# MCU.net
KiCad netlist of a schematic drawn in Altium Designer
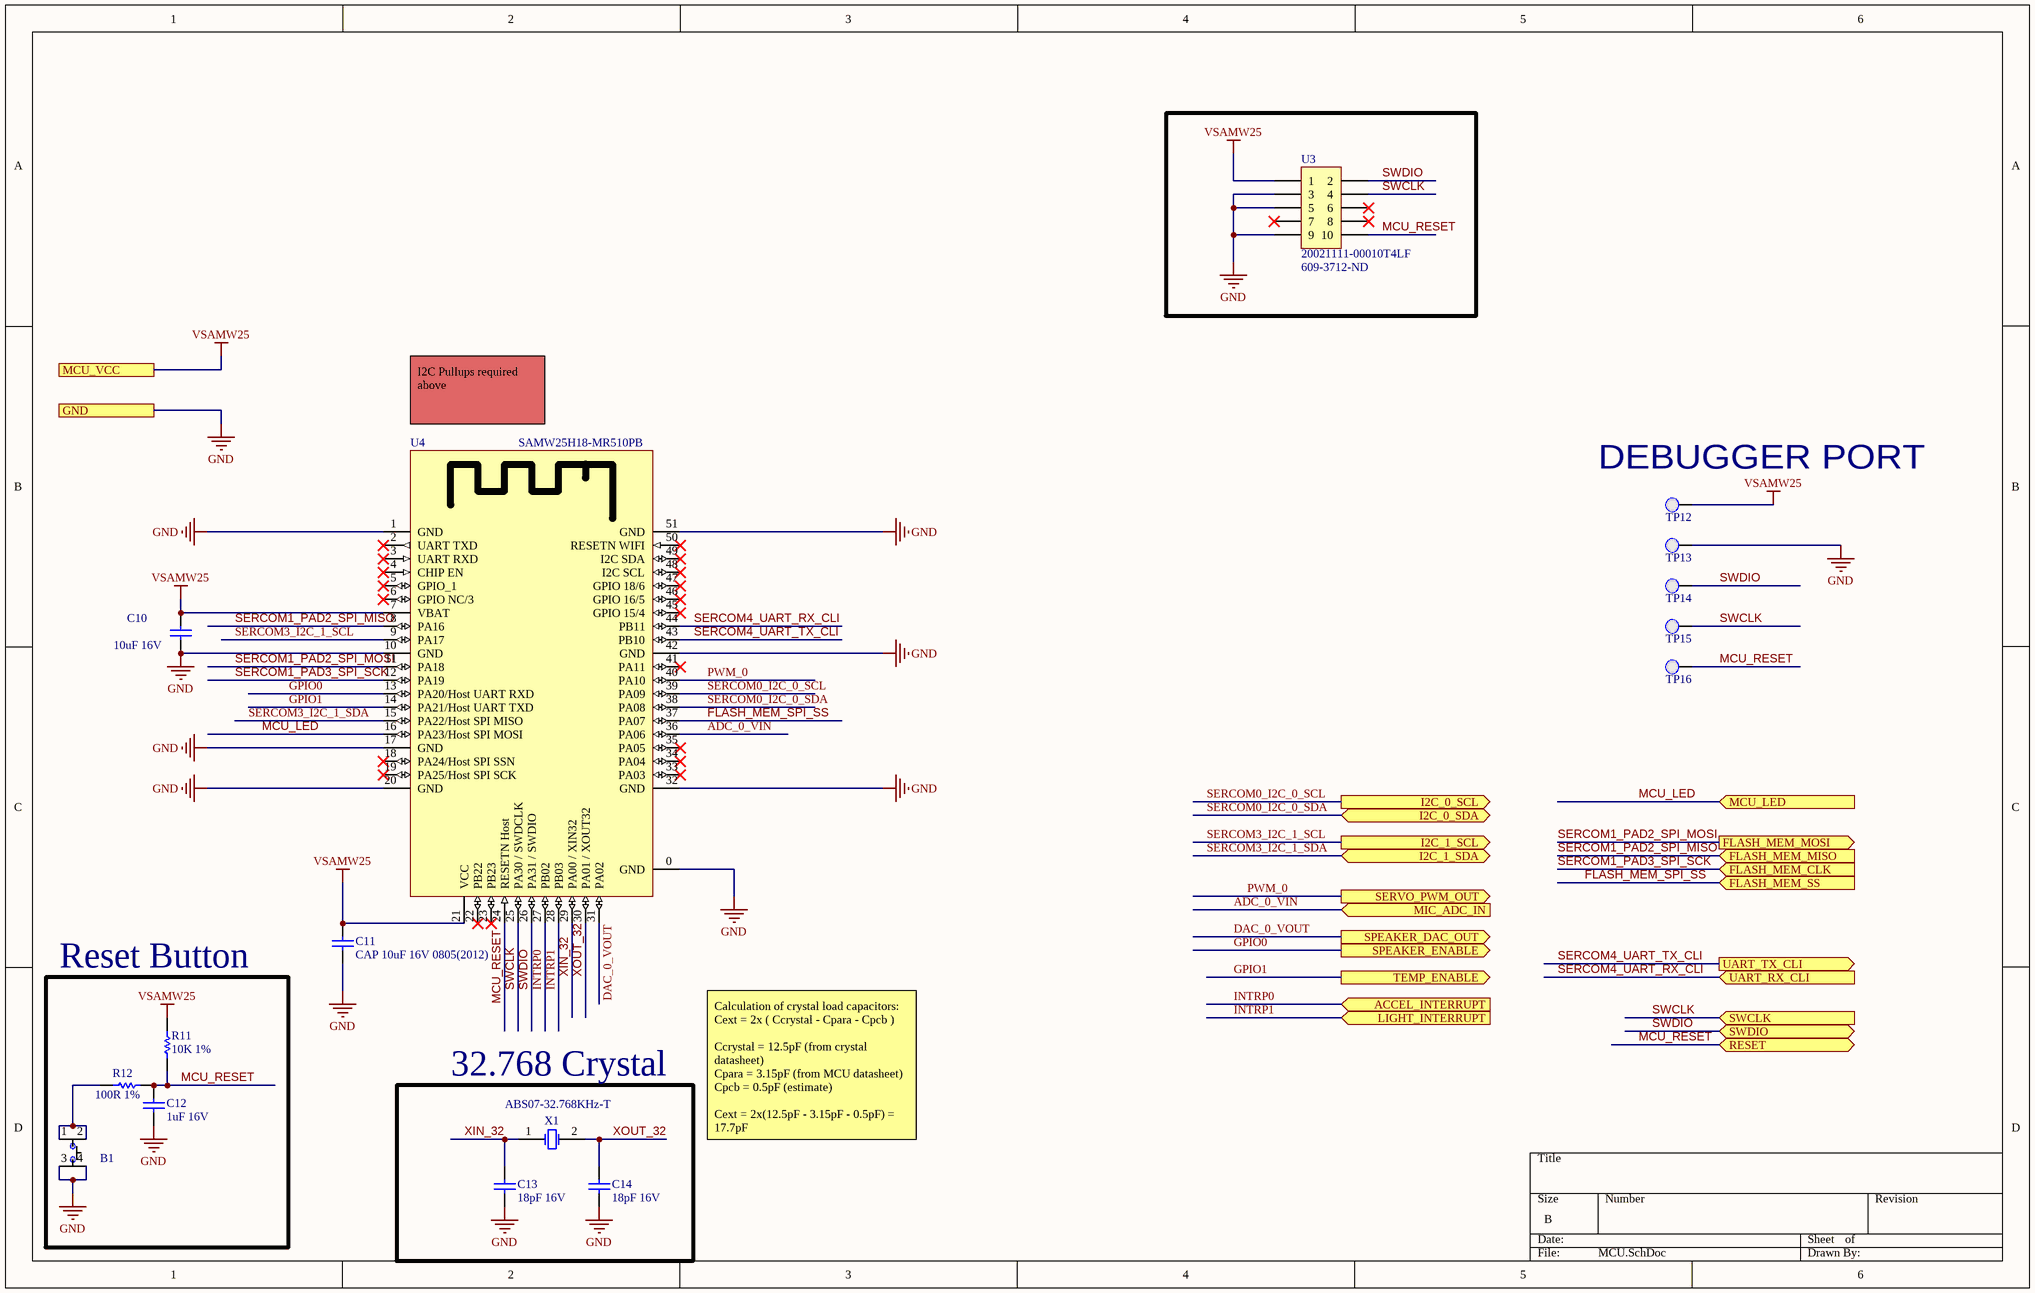
[diagram p0: MCU.SchDoc]

(export (version "E")
  (design (tool "Eeschema 10.0.6"))
  (components
    (comp (ref "B1")
      (value "PTS810 SJK 250 SMTR LFS")
      (footprint "PTS810 SJK 250 SMTR LFS")
      (description "SWITCH TACTILE SPST-NO 0.05A 16V Tactile Switch SPST-NO Top Actuated Surface Mount")
      (fields
        (field (name "MANUFACTURER") "ITT /  C&K Components")
        (field (name "MANUFACTURER PART NUMBER") "PTS810SJK250SMTRLFS")
      )
      (libsource (lib "Schematics") (part "PTS810 SJK 250 SMTR LFS"))
    )
    (comp (ref "C10")
      (value "10uF 16V")
      (footprint "CAPC0805(2012)145_N")
      (description "CAP 10uF 16V ±10% 0805 (2012 Metric) Thickness 1.45mm SMD")
      (fields (field (name "TOLERANCE") "Â±10%"))
      (libsource (lib "Altium Content Vault") (part "CAP"))
    )
    (comp (ref "C11")
      (value "CAP 10uF 16V 0805(2012)")
      (footprint "CAPC0805(2012)145_N")
      (description "CAP 10uF 16V ±10% 0805 (2012 Metric) Thickness 1.45mm SMD")
      (fields (field (name "TOLERANCE") "Â±10%"))
      (libsource (lib "Altium Content Vault") (part "CAP"))
    )
    (comp (ref "C12")
      (value "1uF 16V")
      (footprint "CAPC0603(1608)100_N")
      (description "CAP 1uF 16V ±5% 0603 (1608 Metric) Thickness 1mm SMD")
      (fields (field (name "TOLERANCE") "Â±5%"))
      (libsource (lib "Altium Content Vault") (part "CAP"))
    )
    (comp (ref "C13")
      (value "18pF 16V")
      (footprint "CAPC0603(1608)100_N")
      (description "CAP 18pF 16V ±5% 0603 (1608 Metric) Thickness 1mm SMD")
      (fields (field (name "TOLERANCE") "Â±5%"))
      (libsource (lib "Altium Content Vault") (part "CAP"))
    )
    (comp (ref "C14")
      (value "18pF 16V")
      (footprint "CAPC0603(1608)100_N")
      (description "CAP 18pF 16V ±5% 0603 (1608 Metric) Thickness 1mm SMD")
      (fields (field (name "TOLERANCE") "Â±5%"))
      (libsource (lib "Altium Content Vault") (part "CAP"))
    )
    (comp (ref "R11")
      (value "10K 1%")
      (footprint "RESC0603(1608)_N")
      (description "10K 0.1W 1% 0603 (1608 Metric)  SMD")
      (fields (field (name "POWER") "0.1 W") (field (name "TOLERANCE") "1 %"))
      (libsource (lib "Altium Content Vault") (part "RES"))
    )
    (comp (ref "R12")
      (value "100R 1%")
      (footprint "RESC0603(1608)_N")
      (description "100R 0.1W 1% 0603 (1608 Metric)  SMD")
      (fields (field (name "TOLERANCE") "1 %") (field (name "POWER") "0.1 W"))
      (libsource (lib "Altium Content Vault") (part "RES"))
    )
    (comp (ref "TP12")
      (value "0.1\" Pad")
      (footprint "PCBComponent")
      (libsource (lib "Components - 12.02.20 - 18.05") (part "0.1{dblquote} Pad-A.4"))
    )
    (comp (ref "TP13")
      (value "0.1\" Pad")
      (footprint "PCBComponent")
      (libsource (lib "Components - 12.02.20 - 18.05") (part "0.1{dblquote} Pad-A.4"))
    )
    (comp (ref "TP14")
      (value "0.1\" Pad")
      (footprint "PCBComponent")
      (libsource (lib "Components - 12.02.20 - 18.05") (part "0.1{dblquote} Pad-A.4"))
    )
    (comp (ref "TP15")
      (value "0.1\" Pad")
      (footprint "PCBComponent")
      (libsource (lib "Components - 12.02.20 - 18.05") (part "0.1{dblquote} Pad-A.4"))
    )
    (comp (ref "TP16")
      (value "0.1\" Pad")
      (footprint "PCBComponent")
      (libsource (lib "Components - 12.02.20 - 18.05") (part "0.1{dblquote} Pad-A.4"))
    )
    (comp (ref "U3")
      (value "20021111-00010T4LF")
      (footprint "20021111-00010T4LF")
      (description "CONN HEADER 10POS UNSHD VERT T/H")
      (fields
        (field (name "MANUFACTURER") "Amphenol / FCI")
        (field (name "SUPPLIER PART NUMBER 1") "609-3712-ND")
      )
      (libsource (lib "Schematics") (part "20021111-00010T4LF"))
    )
    (comp (ref "U4")
      (value "SAMW25H18-MR510PB")
      (footprint "SAMW25H18-MR510PB")
      (description "RF TXRX MODULE WIFI TRACE ANT")
      (fields
        (field (name "MANUFACTURER") "Atmel")
        (field (name "MANUFACTURER PART NUMBER") "ATSAMW25H18-MR510PB")
      )
      (libsource (lib "Schematics") (part "SAMW25H18-MR510PB"))
    )
    (comp (ref "X1")
      (value "ABS07-32.768KHz-T")
      (footprint "ABRA-ABS07-2_V")
      (description "Crystal, 32.768 kHz, 12.5 pF, -40 to 85 degC, SMD Low Profile 3.2 x 1.5 x 0.9 mm, Tape and Reel")
      (fields (field (name "MANUFACTURER") "Abracon"))
      (libsource (lib "Altium Content Vault") (part "ABRA-ABS07-2"))
    )
  )
  (nets
    (net (code "1") (name "/ADC_0_VIN") (class "Default")
      (node (ref "U4") (pin "36") (pinfunction "PA06_36") (pintype "bidirectional"))
    )
    (net (code "2") (name "/DAC_0_VOUT") (class "Default")
      (node (ref "U4") (pin "31") (pinfunction "PA02_31") (pintype "bidirectional"))
    )
    (net (code "3") (name "/FLASH_MEM_SPI_SS") (class "Default")
      (node (ref "U4") (pin "37") (pinfunction "PA07_37") (pintype "bidirectional"))
    )
    (net (code "4") (name "/GPIO0") (class "Default")
      (node (ref "U4") (pin "13") (pinfunction "PA20/Host_UART_RXD_13") (pintype "bidirectional"))
    )
    (net (code "5") (name "/GPIO1") (class "Default")
      (node (ref "U4") (pin "14") (pinfunction "PA21/Host_UART_TXD_14") (pintype "bidirectional"))
    )
    (net (code "6") (name "/INTRP0") (class "Default")
      (node (ref "U4") (pin "27") (pinfunction "PB02_27") (pintype "bidirectional"))
    )
    (net (code "7") (name "/INTRP1") (class "Default")
      (node (ref "U4") (pin "28") (pinfunction "PB03_28") (pintype "bidirectional"))
    )
    (net (code "8") (name "/MCU_LED") (class "Default")
      (node (ref "U4") (pin "16") (pinfunction "PA23/Host_SPI_MOSI_16") (pintype "bidirectional"))
    )
    (net (code "9") (name "/MCU_RESET") (class "Default")
      (node (ref "C12") (pin "2") (pinfunction "2_2") (pintype "passive"))
      (node (ref "R11") (pin "1") (pinfunction "1_1") (pintype "passive"))
      (node (ref "R12") (pin "2") (pinfunction "2_2") (pintype "passive"))
      (node (ref "TP16") (pin "1") (pinfunction "PAD_1") (pintype "passive"))
      (node (ref "U3") (pin "10") (pinfunction "10_10") (pintype "passive"))
      (node (ref "U4") (pin "24") (pinfunction "RESETN_Host_24") (pintype "input"))
    )
    (net (code "10") (name "/PWM_0") (class "Default")
      (node (ref "U4") (pin "40") (pinfunction "PA10_40") (pintype "bidirectional"))
    )
    (net (code "11") (name "/SERCOM0_I2C_0_SCL") (class "Default")
      (node (ref "U4") (pin "39") (pinfunction "PA09_39") (pintype "bidirectional"))
    )
    (net (code "12") (name "/SERCOM0_I2C_0_SDA") (class "Default")
      (node (ref "U4") (pin "38") (pinfunction "PA08_38") (pintype "bidirectional"))
    )
    (net (code "13") (name "/SERCOM1_PAD2_SPI_MISO") (class "Default")
      (node (ref "U4") (pin "8") (pinfunction "PA16_8") (pintype "bidirectional"))
    )
    (net (code "14") (name "/SERCOM1_PAD2_SPI_MOSI") (class "Default")
      (node (ref "U4") (pin "11") (pinfunction "PA18_11") (pintype "bidirectional"))
    )
    (net (code "15") (name "/SERCOM1_PAD3_SPI_SCK") (class "Default")
      (node (ref "U4") (pin "12") (pinfunction "PA19_12") (pintype "bidirectional"))
    )
    (net (code "16") (name "/SERCOM3_I2C_1_SCL") (class "Default")
      (node (ref "U4") (pin "9") (pinfunction "PA17_9") (pintype "bidirectional"))
    )
    (net (code "17") (name "/SERCOM3_I2C_1_SDA") (class "Default")
      (node (ref "U4") (pin "15") (pinfunction "PA22/Host_SPI_MISO_15") (pintype "bidirectional"))
    )
    (net (code "18") (name "/SERCOM4_UART_RX_CLI") (class "Default")
      (node (ref "U4") (pin "44") (pinfunction "PB11_44") (pintype "bidirectional"))
    )
    (net (code "19") (name "/SERCOM4_UART_TX_CLI") (class "Default")
      (node (ref "U4") (pin "43") (pinfunction "PB10_43") (pintype "bidirectional"))
    )
    (net (code "20") (name "/SWCLK") (class "Default")
      (node (ref "TP15") (pin "1") (pinfunction "PAD_1") (pintype "passive"))
      (node (ref "U3") (pin "4") (pinfunction "4_4") (pintype "passive"))
      (node (ref "U4") (pin "25") (pinfunction "PA30_/_SWDCLK_25") (pintype "bidirectional"))
    )
    (net (code "21") (name "/SWDIO") (class "Default")
      (node (ref "TP14") (pin "1") (pinfunction "PAD_1") (pintype "passive"))
      (node (ref "U3") (pin "2") (pinfunction "2_2") (pintype "passive"))
      (node (ref "U4") (pin "26") (pinfunction "PA31_/_SWDIO_26") (pintype "bidirectional"))
    )
    (net (code "22") (name "/XIN_32") (class "Default")
      (node (ref "C13") (pin "2") (pinfunction "2_2") (pintype "passive"))
      (node (ref "U4") (pin "29") (pinfunction "PA00_/_XIN32_29") (pintype "bidirectional"))
      (node (ref "X1") (pin "1") (pinfunction "X1_1") (pintype "passive"))
    )
    (net (code "23") (name "/XOUT_32") (class "Default")
      (node (ref "C14") (pin "2") (pinfunction "2_2") (pintype "passive"))
      (node (ref "U4") (pin "30") (pinfunction "PA01_/_XOUT32_30") (pintype "bidirectional"))
      (node (ref "X1") (pin "2") (pinfunction "X2_2") (pintype "passive"))
    )
    (net (code "24") (name "GND") (class "Default")
      (node (ref "B1") (pin "3") (pinfunction "3_3") (pintype "power_in"))
      (node (ref "B1") (pin "4") (pinfunction "4_4") (pintype "power_in"))
      (node (ref "C10") (pin "1") (pinfunction "1_1") (pintype "passive"))
      (node (ref "C11") (pin "1") (pinfunction "1_1") (pintype "passive"))
      (node (ref "C12") (pin "1") (pinfunction "1_1") (pintype "passive"))
      (node (ref "C13") (pin "1") (pinfunction "1_1") (pintype "passive"))
      (node (ref "C14") (pin "1") (pinfunction "1_1") (pintype "passive"))
      (node (ref "TP13") (pin "1") (pinfunction "PAD_1") (pintype "passive"))
      (node (ref "U3") (pin "3") (pinfunction "3_3") (pintype "passive"))
      (node (ref "U3") (pin "5") (pinfunction "5_5") (pintype "passive"))
      (node (ref "U3") (pin "9") (pinfunction "9_9") (pintype "passive"))
      (node (ref "U4") (pin "0") (pinfunction "GND_0") (pintype "power_in"))
      (node (ref "U4") (pin "1") (pinfunction "GND_1") (pintype "power_in"))
      (node (ref "U4") (pin "10") (pinfunction "GND_10") (pintype "power_in"))
      (node (ref "U4") (pin "17") (pinfunction "GND_17") (pintype "power_in"))
      (node (ref "U4") (pin "20") (pinfunction "GND_20") (pintype "power_in"))
      (node (ref "U4") (pin "32") (pinfunction "GND_32") (pintype "power_in"))
      (node (ref "U4") (pin "42") (pinfunction "GND_42") (pintype "power_in"))
      (node (ref "U4") (pin "51") (pinfunction "GND_51") (pintype "power_in"))
    )
    (net (code "25") (name "Net-(B1-Pad1)") (class "Default")
      (node (ref "B1") (pin "1") (pinfunction "1_1") (pintype "power_in"))
      (node (ref "B1") (pin "2") (pinfunction "2_2") (pintype "power_in"))
      (node (ref "R12") (pin "1") (pinfunction "1_1") (pintype "passive"))
    )
    (net (code "26") (name "VSAMW25") (class "Default")
      (node (ref "C10") (pin "2") (pinfunction "2_2") (pintype "passive"))
      (node (ref "C11") (pin "2") (pinfunction "2_2") (pintype "passive"))
      (node (ref "R11") (pin "2") (pinfunction "2_2") (pintype "passive"))
      (node (ref "TP12") (pin "1") (pinfunction "PAD_1") (pintype "passive"))
      (node (ref "U3") (pin "1") (pinfunction "1_1") (pintype "passive"))
      (node (ref "U4") (pin "21") (pinfunction "VCC_21") (pintype "power_in"))
      (node (ref "U4") (pin "7") (pinfunction "VBAT_7") (pintype "power_in"))
    )
    (net (code "27") (name "unconnected-(U3-Pad6)") (class "Default")
      (node (ref "U3") (pin "6") (pinfunction "6_6") (pintype "passive+no_connect"))
    )
    (net (code "28") (name "unconnected-(U3-Pad7)") (class "Default")
      (node (ref "U3") (pin "7") (pinfunction "7_7") (pintype "passive+no_connect"))
    )
    (net (code "29") (name "unconnected-(U3-Pad8)") (class "Default")
      (node (ref "U3") (pin "8") (pinfunction "8_8") (pintype "passive+no_connect"))
    )
    (net (code "30") (name "unconnected-(U4-CHIP_EN-Pad4)") (class "Default")
      (node (ref "U4") (pin "4") (pinfunction "CHIP_EN_4") (pintype "input+no_connect"))
    )
    (net (code "31") (name "unconnected-(U4-GPIO_1-Pad5)") (class "Default")
      (node (ref "U4") (pin "5") (pinfunction "GPIO_1_5") (pintype "bidirectional+no_connect"))
    )
    (net (code "32") (name "unconnected-(U4-GPIO_15{slash}4-Pad45)") (class "Default")
      (node (ref "U4") (pin "45") (pinfunction "GPIO_15/4_45") (pintype "bidirectional+no_connect"))
    )
    (net (code "33") (name "unconnected-(U4-GPIO_16{slash}5-Pad46)") (class "Default")
      (node (ref "U4") (pin "46") (pinfunction "GPIO_16/5_46") (pintype "bidirectional+no_connect"))
    )
    (net (code "34") (name "unconnected-(U4-GPIO_18{slash}6-Pad47)") (class "Default")
      (node (ref "U4") (pin "47") (pinfunction "GPIO_18/6_47") (pintype "bidirectional+no_connect"))
    )
    (net (code "35") (name "unconnected-(U4-GPIO_NC{slash}3-Pad6)") (class "Default")
      (node (ref "U4") (pin "6") (pinfunction "GPIO_NC/3_6") (pintype "bidirectional+no_connect"))
    )
    (net (code "36") (name "unconnected-(U4-I2C_SCL-Pad48)") (class "Default")
      (node (ref "U4") (pin "48") (pinfunction "I2C_SCL_48") (pintype "bidirectional+no_connect"))
    )
    (net (code "37") (name "unconnected-(U4-I2C_SDA-Pad49)") (class "Default")
      (node (ref "U4") (pin "49") (pinfunction "I2C_SDA_49") (pintype "bidirectional+no_connect"))
    )
    (net (code "38") (name "unconnected-(U4-PA03-Pad33)") (class "Default")
      (node (ref "U4") (pin "33") (pinfunction "PA03_33") (pintype "bidirectional+no_connect"))
    )
    (net (code "39") (name "unconnected-(U4-PA04-Pad34)") (class "Default")
      (node (ref "U4") (pin "34") (pinfunction "PA04_34") (pintype "bidirectional+no_connect"))
    )
    (net (code "40") (name "unconnected-(U4-PA05-Pad35)") (class "Default")
      (node (ref "U4") (pin "35") (pinfunction "PA05_35") (pintype "bidirectional+no_connect"))
    )
    (net (code "41") (name "unconnected-(U4-PA11-Pad41)") (class "Default")
      (node (ref "U4") (pin "41") (pinfunction "PA11_41") (pintype "bidirectional+no_connect"))
    )
    (net (code "42") (name "unconnected-(U4-PA24{slash}Host_SPI_SSN-Pad18)") (class "Default")
      (node (ref "U4") (pin "18") (pinfunction "PA24/Host_SPI_SSN_18") (pintype "bidirectional+no_connect"))
    )
    (net (code "43") (name "unconnected-(U4-PA25{slash}Host_SPI_SCK-Pad19)") (class "Default")
      (node (ref "U4") (pin "19") (pinfunction "PA25/Host_SPI_SCK_19") (pintype "bidirectional+no_connect"))
    )
    (net (code "44") (name "unconnected-(U4-PB22-Pad22)") (class "Default")
      (node (ref "U4") (pin "22") (pinfunction "PB22_22") (pintype "bidirectional+no_connect"))
    )
    (net (code "45") (name "unconnected-(U4-PB23-Pad23)") (class "Default")
      (node (ref "U4") (pin "23") (pinfunction "PB23_23") (pintype "bidirectional+no_connect"))
    )
    (net (code "46") (name "unconnected-(U4-RESETN_WIFI-Pad50)") (class "Default")
      (node (ref "U4") (pin "50") (pinfunction "RESETN_WIFI_50") (pintype "input+no_connect"))
    )
    (net (code "47") (name "unconnected-(U4-UART_RXD-Pad3)") (class "Default")
      (node (ref "U4") (pin "3") (pinfunction "UART_RXD_3") (pintype "input+no_connect"))
    )
    (net (code "48") (name "unconnected-(U4-UART_TXD-Pad2)") (class "Default")
      (node (ref "U4") (pin "2") (pinfunction "UART_TXD_2") (pintype "output+no_connect"))
    )
  )
)
